# COMS0004_SwC_Main.net
KiCad netlist of a schematic drawn in Altium Designer
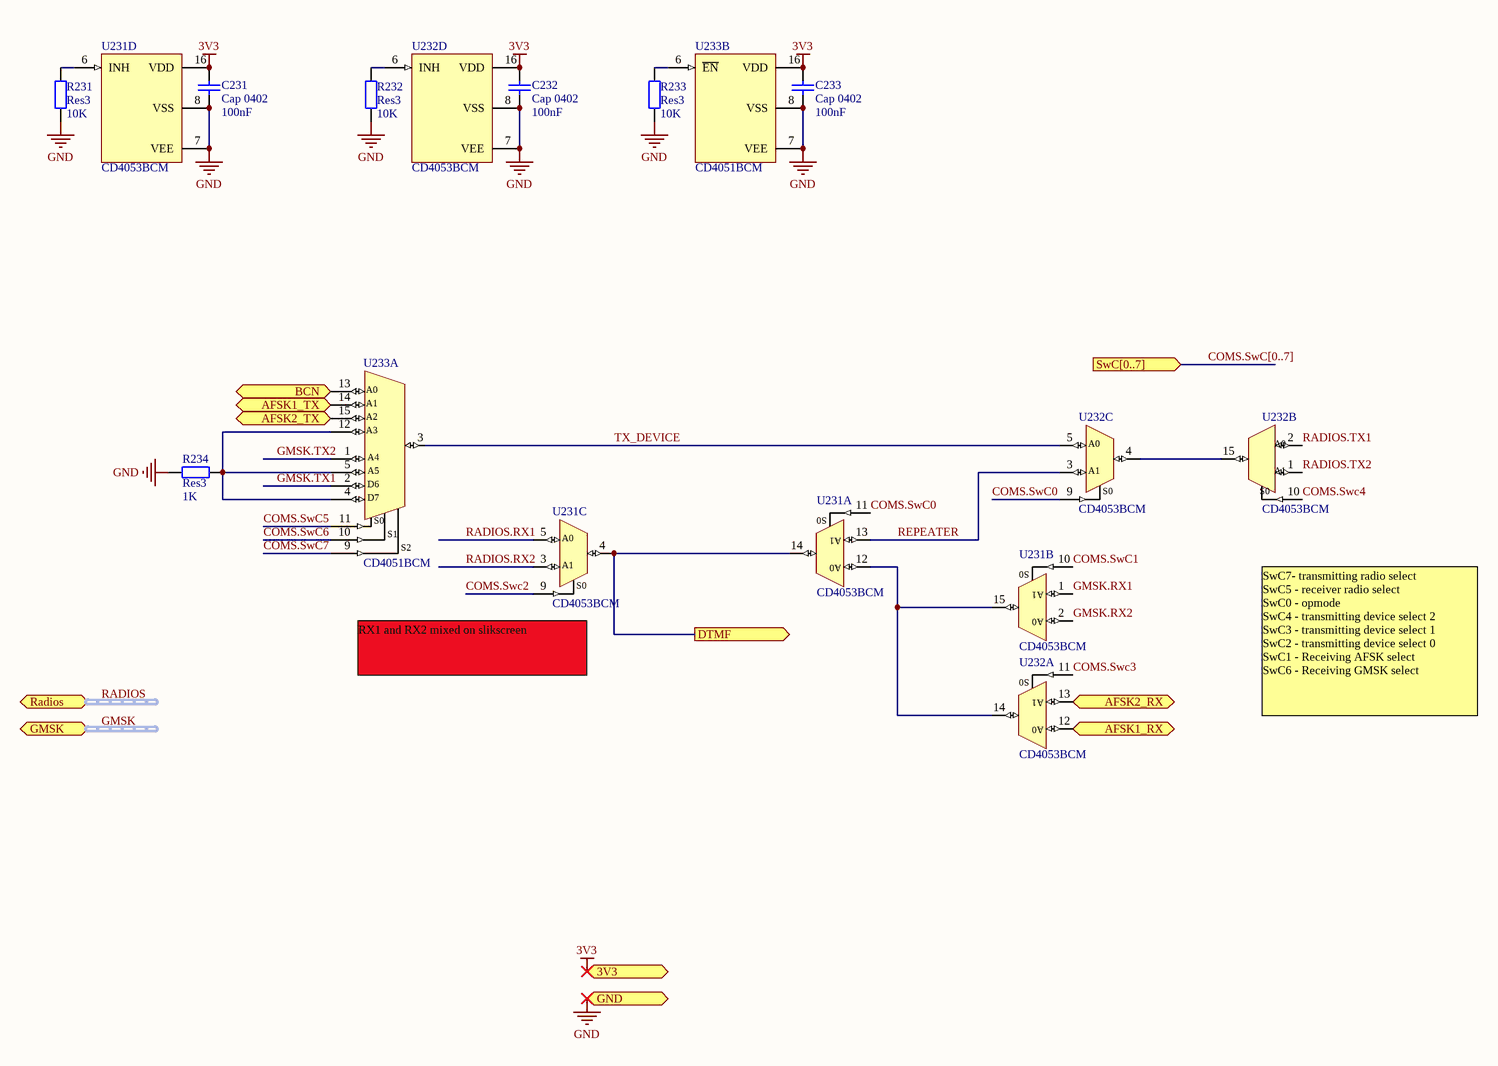
[diagram p0: COMS0004 SwC_Main.SchDoc]

(export (version "E")
  (design (tool "Eeschema 10.0.6"))
  (components
    (comp (ref "C231")
      (value "Cap 0402")
      (footprint "CAPC1005X06L")
      (description "Capacitor")
      (fields (field (name "ALTIUM_VALUE") "100nF") (field (name "PUBLISHER") "Altium Limited"))
      (libsource (lib "CSC") (part "Cap 0402"))
    )
    (comp (ref "C232")
      (value "Cap 0402")
      (footprint "CAPC1005X06L")
      (description "Capacitor")
      (fields (field (name "ALTIUM_VALUE") "100nF") (field (name "PUBLISHER") "Altium Limited"))
      (libsource (lib "CSC") (part "Cap 0402"))
    )
    (comp (ref "C233")
      (value "Cap 0402")
      (footprint "CAPC1005X06L")
      (description "Capacitor")
      (fields (field (name "ALTIUM_VALUE") "100nF") (field (name "PUBLISHER") "Altium Limited"))
      (libsource (lib "CSC") (part "Cap 0402"))
    )
    (comp (ref "R231")
      (value "Res3")
      (footprint "RESC1005X06L")
      (description "Resistor")
      (fields (field (name "ALTIUM_VALUE") "10K") (field (name "PUBLISHER") "Altium Limited"))
      (libsource (lib "CSC") (part "Res3"))
    )
    (comp (ref "R232")
      (value "Res3")
      (footprint "RESC1005X06L")
      (description "Resistor")
      (fields (field (name "ALTIUM_VALUE") "10K") (field (name "PUBLISHER") "Altium Limited"))
      (libsource (lib "CSC") (part "Res3"))
    )
    (comp (ref "R233")
      (value "Res3")
      (footprint "RESC1005X06L")
      (description "Resistor")
      (fields (field (name "ALTIUM_VALUE") "10K") (field (name "PUBLISHER") "Altium Limited"))
      (libsource (lib "CSC") (part "Res3"))
    )
    (comp (ref "R234")
      (value "Res3")
      (footprint "RESC1005X06L")
      (description "Resistor")
      (fields (field (name "ALTIUM_VALUE") "1K") (field (name "PUBLISHER") "Altium Limited"))
      (libsource (lib "") (part "Res3_1"))
    )
    (comp (ref "U231")
      (value "CD4053BCM")
      (footprint "Comms Board Small Footprints:TSSOP16")
      (description "Triple 2-Channnel Analog Multiplexer/Demutiplexer")
      (libsource (lib "Comms Board Small Footprints") (part "CD4053BCM"))
    )
    (comp (ref "U232")
      (value "CD4053BCM")
      (footprint "Comms Board Small Footprints:TSSOP16")
      (description "Triple 2-Channnel Analog Multiplexer/Demutiplexer")
      (libsource (lib "") (part "CD4053BCM_1"))
    )
    (comp (ref "U233")
      (value "CD4051BCM")
      (footprint "Comms Board Small Footprints:TSSOP16")
      (description "8-Channel Analog Multiplexer/Demultiplexer")
      (libsource (lib "") (part "CD4051BCM_1"))
    )
  )
  (nets
    (net (code "6") (name "/AFSK1_RX") (class "Default")
      (node (ref "U232") (pin "12") (pinfunction "A0_12") (pintype "bidirectional"))
    )
    (net (code "7") (name "/AFSK1_TX") (class "Default")
      (node (ref "U233") (pin "14") (pinfunction "A1_14") (pintype "bidirectional"))
    )
    (net (code "8") (name "/AFSK2_RX") (class "Default")
      (node (ref "U232") (pin "13") (pinfunction "A1_13") (pintype "bidirectional"))
    )
    (net (code "9") (name "/AFSK2_TX") (class "Default")
      (node (ref "U233") (pin "15") (pinfunction "A2_15") (pintype "bidirectional"))
    )
    (net (code "10") (name "/BCN") (class "Default")
      (node (ref "U233") (pin "13") (pinfunction "A0_13") (pintype "bidirectional"))
    )
    (net (code "11") (name "/COMS.SwC0") (class "Default")
      (node (ref "U231") (pin "11") (pinfunction "A_11") (pintype "input"))
      (node (ref "U232") (pin "9") (pinfunction "C_9") (pintype "input"))
    )
    (net (code "12") (name "/COMS.SwC1") (class "Default")
      (node (ref "U231") (pin "10") (pinfunction "B_10") (pintype "input"))
    )
    (net (code "13") (name "/COMS.SwC5") (class "Default")
      (node (ref "U233") (pin "11") (pinfunction "S0_11") (pintype "input"))
    )
    (net (code "14") (name "/COMS.SwC6") (class "Default")
      (node (ref "U233") (pin "10") (pinfunction "S1_10") (pintype "input"))
    )
    (net (code "15") (name "/COMS.SwC7") (class "Default")
      (node (ref "U233") (pin "9") (pinfunction "S2_9") (pintype "input"))
    )
    (net (code "17") (name "/COMS.Swc2") (class "Default")
      (node (ref "U231") (pin "9") (pinfunction "C_9") (pintype "input"))
    )
    (net (code "18") (name "/COMS.Swc3") (class "Default")
      (node (ref "U232") (pin "11") (pinfunction "A_11") (pintype "input"))
    )
    (net (code "19") (name "/COMS.Swc4") (class "Default")
      (node (ref "U232") (pin "10") (pinfunction "B_10") (pintype "input"))
    )
    (net (code "20") (name "/DTMF") (class "Default")
      (node (ref "U231") (pin "14") (pinfunction "A_out_14") (pintype "bidirectional"))
      (node (ref "U231") (pin "4") (pinfunction "c_out_4") (pintype "bidirectional"))
    )
    (net (code "21") (name "/GMSK.RX1") (class "Default")
      (node (ref "U231") (pin "1") (pinfunction "by_1") (pintype "bidirectional"))
    )
    (net (code "22") (name "/GMSK.RX2") (class "Default")
      (node (ref "U231") (pin "2") (pinfunction "bx_2") (pintype "bidirectional"))
    )
    (net (code "23") (name "/GMSK.TX1") (class "Default")
      (node (ref "U233") (pin "2") (pinfunction "A6_2") (pintype "bidirectional"))
    )
    (net (code "24") (name "/GMSK.TX2") (class "Default")
      (node (ref "U233") (pin "1") (pinfunction "A4_1") (pintype "bidirectional"))
    )
    (net (code "25") (name "/RADIOS.RX1") (class "Default")
      (node (ref "U231") (pin "5") (pinfunction "cx_5") (pintype "bidirectional"))
    )
    (net (code "26") (name "/RADIOS.RX2") (class "Default")
      (node (ref "U231") (pin "3") (pinfunction "cy_3") (pintype "bidirectional"))
    )
    (net (code "27") (name "/RADIOS.TX1") (class "Default")
      (node (ref "U232") (pin "2") (pinfunction "bx_2") (pintype "bidirectional"))
    )
    (net (code "28") (name "/RADIOS.TX2") (class "Default")
      (node (ref "U232") (pin "1") (pinfunction "by_1") (pintype "bidirectional"))
    )
    (net (code "29") (name "/REPEATER") (class "Default")
      (node (ref "U231") (pin "13") (pinfunction "A1_13") (pintype "bidirectional"))
      (node (ref "U232") (pin "3") (pinfunction "cy_3") (pintype "bidirectional"))
    )
    (net (code "30") (name "/TX_DEVICE") (class "Default")
      (node (ref "U232") (pin "5") (pinfunction "cx_5") (pintype "bidirectional"))
      (node (ref "U233") (pin "3") (pinfunction "O_3") (pintype "bidirectional"))
    )
    (net (code "33") (name "3V3") (class "Default")
      (node (ref "C231") (pin "2") (pinfunction "2_2") (pintype "passive"))
      (node (ref "C232") (pin "2") (pinfunction "2_2") (pintype "passive"))
      (node (ref "C233") (pin "2") (pinfunction "2_2") (pintype "passive"))
      (node (ref "U231") (pin "16") (pinfunction "VDD_16") (pintype "power_in"))
      (node (ref "U232") (pin "16") (pinfunction "VDD_16") (pintype "power_in"))
      (node (ref "U233") (pin "16") (pinfunction "VDD_16") (pintype "power_in"))
    )
    (net (code "34") (name "GND") (class "Default")
      (node (ref "C231") (pin "1") (pinfunction "1_1") (pintype "passive"))
      (node (ref "C232") (pin "1") (pinfunction "1_1") (pintype "passive"))
      (node (ref "C233") (pin "1") (pinfunction "1_1") (pintype "passive"))
      (node (ref "R231") (pin "2") (pinfunction "2_2") (pintype "passive"))
      (node (ref "R232") (pin "2") (pinfunction "2_2") (pintype "passive"))
      (node (ref "R233") (pin "2") (pinfunction "2_2") (pintype "passive"))
      (node (ref "R234") (pin "1") (pinfunction "1_1") (pintype "passive"))
      (node (ref "U231") (pin "7") (pinfunction "VEE_7") (pintype "power_in"))
      (node (ref "U231") (pin "8") (pinfunction "VSS_8") (pintype "power_in"))
      (node (ref "U232") (pin "7") (pinfunction "VEE_7") (pintype "power_in"))
      (node (ref "U232") (pin "8") (pinfunction "VSS_8") (pintype "power_in"))
      (node (ref "U233") (pin "7") (pinfunction "VEE_7") (pintype "power_in"))
      (node (ref "U233") (pin "8") (pinfunction "VSS_8") (pintype "power_in"))
    )
    (net (code "35") (name "Net-(U231A-A0)") (class "Default")
      (node (ref "U231") (pin "12") (pinfunction "A0_12") (pintype "bidirectional"))
      (node (ref "U231") (pin "15") (pinfunction "b_out_15") (pintype "bidirectional"))
      (node (ref "U232") (pin "14") (pinfunction "A_out_14") (pintype "bidirectional"))
    )
    (net (code "36") (name "Net-(U231D-INH)") (class "Default")
      (node (ref "R231") (pin "1") (pinfunction "1_1") (pintype "passive"))
      (node (ref "U231") (pin "6") (pinfunction "INH_6") (pintype "input"))
    )
    (net (code "37") (name "Net-(U232B-b_out)") (class "Default")
      (node (ref "U232") (pin "15") (pinfunction "b_out_15") (pintype "bidirectional"))
      (node (ref "U232") (pin "4") (pinfunction "c_out_4") (pintype "bidirectional"))
    )
    (net (code "38") (name "Net-(U232D-INH)") (class "Default")
      (node (ref "R232") (pin "1") (pinfunction "1_1") (pintype "passive"))
      (node (ref "U232") (pin "6") (pinfunction "INH_6") (pintype "input"))
    )
    (net (code "39") (name "Net-(U233A-A3)") (class "Default")
      (node (ref "R234") (pin "2") (pinfunction "2_2") (pintype "passive"))
      (node (ref "U233") (pin "12") (pinfunction "A3_12") (pintype "bidirectional"))
      (node (ref "U233") (pin "4") (pinfunction "A7_4") (pintype "bidirectional"))
      (node (ref "U233") (pin "5") (pinfunction "A5_5") (pintype "bidirectional"))
    )
    (net (code "40") (name "Net-(U233B-~{EN})") (class "Default")
      (node (ref "R233") (pin "1") (pinfunction "1_1") (pintype "passive"))
      (node (ref "U233") (pin "6") (pinfunction "~{EN}_6") (pintype "input"))
    )
  )
)
